# schematic_328.net
KiCad netlist of a schematic drawn in Altium Designer
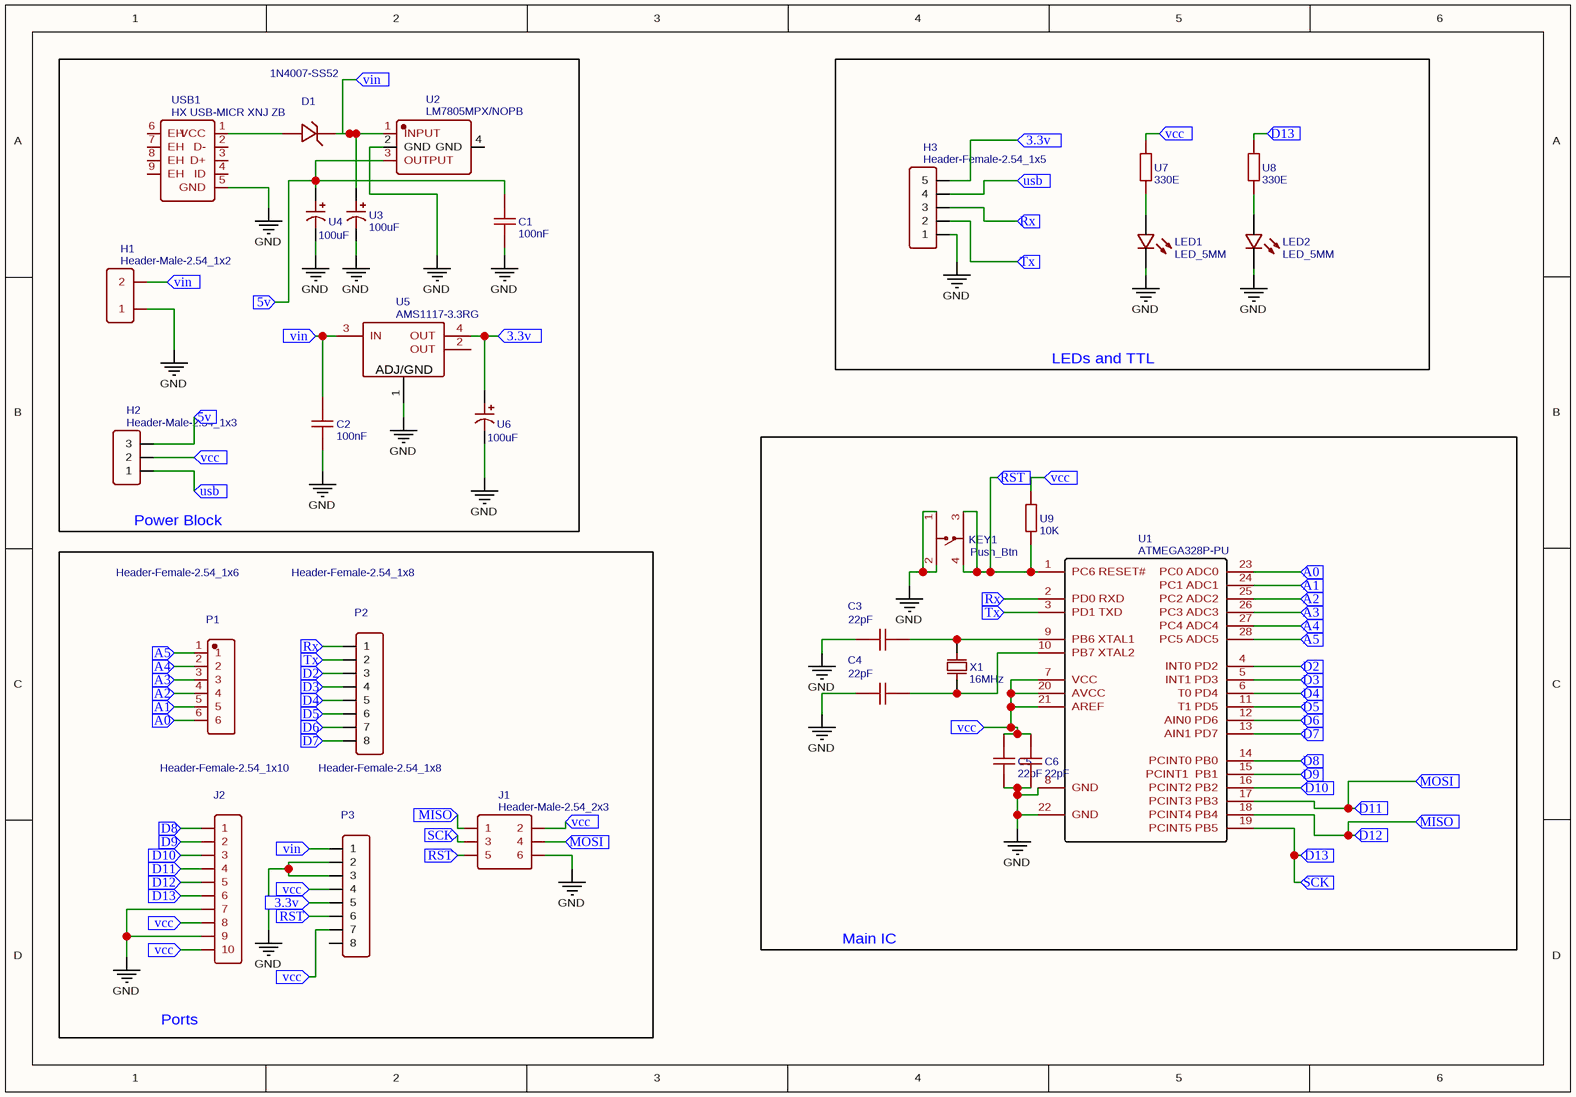
[diagram p0: schematic_328.schdoc]

(export (version "E")
  (design (tool "Eeschema 10.0.6"))
  (components
    (comp (ref "C1")
      (value "100nF")
      (fields
        (field (name "MANUFACTURER") "HRE(芯声)")
        (field (name "MANUFACTURER PART") "CGA1206X7R104K251NT")
        (field (name "CONTRIBUTOR") "lcsc")
      )
      (libsource (lib "altium-import") (part "root_1_100nF_"))
    )
    (comp (ref "C2")
      (value "100nF")
      (fields
        (field (name "MANUFACTURER") "HRE(芯声)")
        (field (name "MANUFACTURER PART") "CGA1206X7R104K251NT")
        (field (name "CONTRIBUTOR") "lcsc")
      )
      (libsource (lib "altium-import") (part "root_1_100nF_"))
    )
    (comp (ref "C3")
      (value "22pF")
      (fields
        (field (name "MANUFACTURER") "HRE(芯声)")
        (field (name "MANUFACTURER PART") "CGA1206X7R104K251NT")
        (field (name "CONTRIBUTOR") "lcsc")
      )
      (libsource (lib "altium-import") (part "root_2_22pF_"))
    )
    (comp (ref "C4")
      (value "22pF")
      (fields
        (field (name "MANUFACTURER") "HRE(芯声)")
        (field (name "MANUFACTURER PART") "CGA1206X7R104K251NT")
        (field (name "CONTRIBUTOR") "lcsc")
      )
      (libsource (lib "altium-import") (part "root_2_22pF_"))
    )
    (comp (ref "C5")
      (value "22pF")
      (fields
        (field (name "MANUFACTURER") "HRE(芯声)")
        (field (name "MANUFACTURER PART") "CGA1206X7R104K251NT")
        (field (name "CONTRIBUTOR") "lcsc")
      )
      (libsource (lib "altium-import") (part "root_3_22pF_"))
    )
    (comp (ref "C6")
      (value "22pF")
      (fields
        (field (name "MANUFACTURER") "HRE(芯声)")
        (field (name "MANUFACTURER PART") "CGA1206X7R104K251NT")
        (field (name "CONTRIBUTOR") "lcsc")
      )
      (libsource (lib "altium-import") (part "root_3_22pF_"))
    )
    (comp (ref "D1")
      (value "1N4007-SS52")
      (fields (field (name "CONTRIBUTOR") "LCSC"))
      (libsource (lib "altium-import") (part "root_2_1N4007-SS52_"))
    )
    (comp (ref "H1")
      (value "Header-Male-2.54_1x2")
      (fields
        (field (name "MANUFACTURER") "TE Connectivity(泰科电子)")
        (field (name "MANUFACTURER PART") "826629-2")
      )
      (libsource (lib "altium-import") (part "root_2_Header-Male-2.54_1x2_"))
    )
    (comp (ref "H2")
      (value "Header-Male-2.54_1x3")
      (fields (field (name "MANUFACTURER") "BOOMELE(博穆精密)") (field (name "MANUFACTURER PART") "2.54-1*3P针"))
      (libsource (lib "altium-import") (part "root_2_Header-Male-2.54_1x3_"))
    )
    (comp (ref "H3")
      (value "Header-Female-2.54_1x5")
      (fields (field (name "MANUFACTURER") "BOOMELE(博穆精密)") (field (name "MANUFACTURER PART") "2.54-1*5P母"))
      (libsource (lib "altium-import") (part "root_2_Header-Female-2.54_1x5_"))
    )
    (comp (ref "J1")
      (value "Header-Male-2.54_2x3")
      (fields (field (name "MANUFACTURER") "BOOMELE(博穆精密)") (field (name "MANUFACTURER PART") "2.54-2*3P针"))
      (libsource (lib "altium-import") (part "root_0_Header-Male-2.54_2x3_"))
    )
    (comp (ref "J2")
      (value "Header-Female-2.54_1x10")
      (fields (field (name "MANUFACTURER") "BOOMELE(博穆精密)") (field (name "MANUFACTURER PART") "2.54-1*10P母"))
      (libsource (lib "altium-import") (part "root_0_Header-Female-2.54_1x10_"))
    )
    (comp (ref "KEY1")
      (value "Push_Btn")
      (fields
        (field (name "MANUFACTURER PART") "4pinTACTPCBTHTPushButton")
        (field (name "CONTRIBUTOR") "LCSC")
      )
      (libsource (lib "altium-import") (part "root_1_Push_Btn_"))
    )
    (comp (ref "LED1")
      (value "LED_5MM")
      (fields (field (name "CONTRIBUTOR") "lcsc"))
      (libsource (lib "altium-import") (part "root_3_LED_5MM_"))
    )
    (comp (ref "LED2")
      (value "LED_5MM")
      (fields (field (name "CONTRIBUTOR") "lcsc"))
      (libsource (lib "altium-import") (part "root_3_LED_5MM_"))
    )
    (comp (ref "P1")
      (value "Header-Female-2.54_1x6")
      (fields (field (name "MANUFACTURER") "BOOMELE(博穆精密)") (field (name "MANUFACTURER PART") "2.54-1*6P母"))
      (libsource (lib "altium-import") (part "root_0_Header-Female-2.54_1x6_"))
    )
    (comp (ref "P2")
      (value "Header-Female-2.54_1x8")
      (fields (field (name "MANUFACTURER") "BOOMELE(博穆精密)") (field (name "MANUFACTURER PART") "2.54-1*8P母环保"))
      (libsource (lib "altium-import") (part "root_0_Header-Female-2.54_1x8_"))
    )
    (comp (ref "P3")
      (value "Header-Female-2.54_1x8")
      (fields (field (name "MANUFACTURER") "BOOMELE(博穆精密)") (field (name "MANUFACTURER PART") "2.54-1*8P母环保"))
      (libsource (lib "altium-import") (part "root_0_Header-Female-2.54_1x8_"))
    )
    (comp (ref "U1")
      (value "ATMEGA328P-PU")
      (fields (field (name "MANUFACTURER") "MICROCHIP(美国微芯)") (field (name "CONTRIBUTOR") "LCSC"))
      (libsource (lib "altium-import") (part "root_0_ATMEGA328P-PU_"))
    )
    (comp (ref "U2")
      (value "LM7805MPX/NOPB")
      (fields (field (name "MANUFACTURER") "TI(德州仪器)") (field (name "CONTRIBUTOR") "LCSC"))
      (libsource (lib "altium-import") (part "root_0_LM7805MPX/NOPB_"))
    )
    (comp (ref "U3")
      (value "100uF")
      (fields
        (field (name "MANUFACTURER") "rubycon(红宝石)")
        (field (name "MANUFACTURER PART") "25YXS100MEFC5X11")
        (field (name "CONTRIBUTOR") "lcsc")
      )
      (libsource (lib "altium-import") (part "root_3_100uF_"))
    )
    (comp (ref "U4")
      (value "100uF")
      (fields
        (field (name "MANUFACTURER") "rubycon(红宝石)")
        (field (name "MANUFACTURER PART") "25YXS100MEFC5X11")
        (field (name "CONTRIBUTOR") "lcsc")
      )
      (libsource (lib "altium-import") (part "root_3_100uF_"))
    )
    (comp (ref "U5")
      (value "AMS1117-3.3RG")
      (fields (field (name "MANUFACTURER") "HGC(深圳汉芯)") (field (name "CONTRIBUTOR") "lcsc"))
      (libsource (lib "altium-import") (part "root_0_AMS1117-3.3RG_"))
    )
    (comp (ref "U6")
      (value "100uF")
      (fields
        (field (name "MANUFACTURER") "rubycon(红宝石)")
        (field (name "MANUFACTURER PART") "25YXS100MEFC5X11")
        (field (name "CONTRIBUTOR") "lcsc")
      )
      (libsource (lib "altium-import") (part "root_3_100uF_"))
    )
    (comp (ref "U7")
      (value "330E")
      (fields (field (name "MANUFACTURER PART") "4703-1206") (field (name "CONTRIBUTOR") "lcsc"))
      (libsource (lib "altium-import") (part "root_1_330E_"))
    )
    (comp (ref "U8")
      (value "330E")
      (fields (field (name "MANUFACTURER PART") "4703-1206") (field (name "CONTRIBUTOR") "lcsc"))
      (libsource (lib "altium-import") (part "root_1_330E_"))
    )
    (comp (ref "U9")
      (value "10K")
      (fields (field (name "MANUFACTURER PART") "4703-1206") (field (name "CONTRIBUTOR") "lcsc"))
      (libsource (lib "altium-import") (part "root_1_10K_"))
    )
    (comp (ref "USB1")
      (value "HX USB-MICR XNJ ZB")
      (fields (field (name "MANUFACTURER") "hanxia(韩下)") (field (name "CONTRIBUTOR") "lcsc"))
      (libsource (lib "altium-import") (part "root_2_HX USB-MICR XNJ ZB_"))
    )
    (comp (ref "X1")
      (value "16MHz")
      (fields
        (field (name "MANUFACTURER") "JGHC(晶光华)")
        (field (name "MANUFACTURER PART") "49SAC16000202060")
        (field (name "CONTRIBUTOR") "LCSC")
      )
      (libsource (lib "altium-import") (part "root_1_16MHz_"))
    )
  )
  (nets
    (net (code "1") (name "/3.3v") (class "Default")
      (node (ref "H3") (pin "5") (pinfunction "5_5") (pintype "passive"))
      (node (ref "P3") (pin "5") (pinfunction "5_5") (pintype "passive"))
      (node (ref "U5") (pin "4") (pinfunction "OUT_4") (pintype "passive"))
      (node (ref "U6") (pin "1") (pinfunction "1_1") (pintype "passive"))
    )
    (net (code "2") (name "/5v") (class "Default")
      (node (ref "C1") (pin "2") (pinfunction "2_2") (pintype "passive"))
      (node (ref "H2") (pin "3") (pinfunction "3_3") (pintype "passive"))
      (node (ref "U2") (pin "3") (pinfunction "OUTPUT_3") (pintype "passive"))
      (node (ref "U4") (pin "1") (pinfunction "1_1") (pintype "passive"))
    )
    (net (code "3") (name "/A0") (class "Default")
      (node (ref "P1") (pin "6") (pinfunction "6_6") (pintype "passive"))
      (node (ref "U1") (pin "23") (pinfunction "PC0_ADC0_23") (pintype "passive"))
    )
    (net (code "4") (name "/A1") (class "Default")
      (node (ref "P1") (pin "5") (pinfunction "5_5") (pintype "passive"))
      (node (ref "U1") (pin "24") (pinfunction "PC1_ADC1_24") (pintype "passive"))
    )
    (net (code "5") (name "/A2") (class "Default")
      (node (ref "P1") (pin "4") (pinfunction "4_4") (pintype "passive"))
      (node (ref "U1") (pin "25") (pinfunction "PC2_ADC2_25") (pintype "passive"))
    )
    (net (code "6") (name "/A3") (class "Default")
      (node (ref "P1") (pin "3") (pinfunction "3_3") (pintype "passive"))
      (node (ref "U1") (pin "26") (pinfunction "PC3_ADC3_26") (pintype "passive"))
    )
    (net (code "7") (name "/A4") (class "Default")
      (node (ref "P1") (pin "2") (pinfunction "2_2") (pintype "passive"))
      (node (ref "U1") (pin "27") (pinfunction "PC4_ADC4_27") (pintype "passive"))
    )
    (net (code "8") (name "/A5") (class "Default")
      (node (ref "P1") (pin "1") (pinfunction "1_1") (pintype "passive"))
      (node (ref "U1") (pin "28") (pinfunction "PC5_ADC5_28") (pintype "passive"))
    )
    (net (code "9") (name "/D2") (class "Default")
      (node (ref "P2") (pin "3") (pinfunction "3_3") (pintype "passive"))
      (node (ref "U1") (pin "4") (pinfunction "INT0_PD2_4") (pintype "passive"))
    )
    (net (code "10") (name "/D3") (class "Default")
      (node (ref "P2") (pin "4") (pinfunction "4_4") (pintype "passive"))
      (node (ref "U1") (pin "5") (pinfunction "INT1_PD3_5") (pintype "passive"))
    )
    (net (code "11") (name "/D4") (class "Default")
      (node (ref "P2") (pin "5") (pinfunction "5_5") (pintype "passive"))
      (node (ref "U1") (pin "6") (pinfunction "T0_PD4_6") (pintype "passive"))
    )
    (net (code "12") (name "/D5") (class "Default")
      (node (ref "P2") (pin "6") (pinfunction "6_6") (pintype "passive"))
      (node (ref "U1") (pin "11") (pinfunction "T1_PD5_11") (pintype "passive"))
    )
    (net (code "13") (name "/D6") (class "Default")
      (node (ref "P2") (pin "7") (pinfunction "7_7") (pintype "passive"))
      (node (ref "U1") (pin "12") (pinfunction "AIN0_PD6_12") (pintype "passive"))
    )
    (net (code "14") (name "/D7") (class "Default")
      (node (ref "P2") (pin "8") (pinfunction "8_8") (pintype "passive"))
      (node (ref "U1") (pin "13") (pinfunction "AIN1_PD7_13") (pintype "passive"))
    )
    (net (code "15") (name "/D8") (class "Default")
      (node (ref "J2") (pin "1") (pinfunction "1_1") (pintype "passive"))
      (node (ref "U1") (pin "14") (pinfunction "PCINT0_PB0_14") (pintype "passive"))
    )
    (net (code "16") (name "/D9") (class "Default")
      (node (ref "J2") (pin "2") (pinfunction "2_2") (pintype "passive"))
      (node (ref "U1") (pin "15") (pinfunction "PCINT1__PB1_15") (pintype "passive"))
    )
    (net (code "17") (name "/D10") (class "Default")
      (node (ref "J2") (pin "3") (pinfunction "3_3") (pintype "passive"))
      (node (ref "U1") (pin "16") (pinfunction "PCINT2_PB2_16") (pintype "passive"))
    )
    (net (code "18") (name "/D11") (class "Default")
      (node (ref "J1") (pin "4") (pinfunction "4_4") (pintype "passive"))
      (node (ref "J2") (pin "4") (pinfunction "4_4") (pintype "passive"))
      (node (ref "U1") (pin "17") (pinfunction "PCINT3_PB3_17") (pintype "passive"))
    )
    (net (code "19") (name "/D12") (class "Default")
      (node (ref "J1") (pin "1") (pinfunction "1_1") (pintype "passive"))
      (node (ref "J2") (pin "5") (pinfunction "5_5") (pintype "passive"))
      (node (ref "U1") (pin "18") (pinfunction "PCINT4_PB4_18") (pintype "passive"))
    )
    (net (code "20") (name "/D13") (class "Default")
      (node (ref "J1") (pin "3") (pinfunction "3_3") (pintype "passive"))
      (node (ref "J2") (pin "6") (pinfunction "6_6") (pintype "passive"))
      (node (ref "U1") (pin "19") (pinfunction "PCINT5_PB5_19") (pintype "passive"))
      (node (ref "U8") (pin "2") (pinfunction "2_2") (pintype "passive"))
    )
    (net (code "21") (name "/RST") (class "Default")
      (node (ref "J1") (pin "5") (pinfunction "5_5") (pintype "passive"))
      (node (ref "KEY1") (pin "3") (pinfunction "3_3") (pintype "passive"))
      (node (ref "KEY1") (pin "4") (pinfunction "4_4") (pintype "passive"))
      (node (ref "P3") (pin "6") (pinfunction "6_6") (pintype "passive"))
      (node (ref "U1") (pin "1") (pinfunction "PC6_RESET#_1") (pintype "passive"))
      (node (ref "U9") (pin "1") (pinfunction "1_1") (pintype "passive"))
    )
    (net (code "22") (name "/Rx") (class "Default")
      (node (ref "H3") (pin "3") (pinfunction "3_3") (pintype "passive"))
      (node (ref "P2") (pin "1") (pinfunction "1_1") (pintype "passive"))
      (node (ref "U1") (pin "2") (pinfunction "PD0_RXD_2") (pintype "passive"))
    )
    (net (code "23") (name "/Tx") (class "Default")
      (node (ref "H3") (pin "2") (pinfunction "2_2") (pintype "passive"))
      (node (ref "P2") (pin "2") (pinfunction "2_2") (pintype "passive"))
      (node (ref "U1") (pin "3") (pinfunction "PD1_TXD_3") (pintype "passive"))
    )
    (net (code "24") (name "/usb") (class "Default")
      (node (ref "H2") (pin "1") (pinfunction "1_1") (pintype "passive"))
      (node (ref "H3") (pin "4") (pinfunction "4_4") (pintype "passive"))
    )
    (net (code "25") (name "/vcc") (class "Default")
      (node (ref "C5") (pin "1") (pinfunction "1_1") (pintype "passive"))
      (node (ref "C6") (pin "1") (pinfunction "1_1") (pintype "passive"))
      (node (ref "H2") (pin "2") (pinfunction "2_2") (pintype "passive"))
      (node (ref "J1") (pin "2") (pinfunction "2_2") (pintype "passive"))
      (node (ref "J2") (pin "10") (pinfunction "10_10") (pintype "passive"))
      (node (ref "J2") (pin "8") (pinfunction "8_8") (pintype "passive"))
      (node (ref "P3") (pin "4") (pinfunction "4_4") (pintype "passive"))
      (node (ref "P3") (pin "7") (pinfunction "7_7") (pintype "passive"))
      (node (ref "U1") (pin "20") (pinfunction "AVCC_20") (pintype "passive"))
      (node (ref "U1") (pin "21") (pinfunction "AREF_21") (pintype "passive"))
      (node (ref "U1") (pin "7") (pinfunction "VCC_7") (pintype "passive"))
      (node (ref "U7") (pin "2") (pinfunction "2_2") (pintype "passive"))
      (node (ref "U9") (pin "2") (pinfunction "2_2") (pintype "passive"))
    )
    (net (code "26") (name "/vin") (class "Default")
      (node (ref "C2") (pin "2") (pinfunction "2_2") (pintype "passive"))
      (node (ref "D1") (pin "1") (pinfunction "C_1") (pintype "passive"))
      (node (ref "H1") (pin "2") (pinfunction "2_2") (pintype "passive"))
      (node (ref "P3") (pin "1") (pinfunction "1_1") (pintype "passive"))
      (node (ref "U2") (pin "1") (pinfunction "INPUT_1") (pintype "passive"))
      (node (ref "U3") (pin "1") (pinfunction "1_1") (pintype "passive"))
      (node (ref "U5") (pin "3") (pinfunction "IN_3") (pintype "passive"))
    )
    (net (code "27") (name "GND") (class "Default")
      (node (ref "C1") (pin "1") (pinfunction "1_1") (pintype "passive"))
      (node (ref "C2") (pin "1") (pinfunction "1_1") (pintype "passive"))
      (node (ref "C3") (pin "2") (pinfunction "2_2") (pintype "passive"))
      (node (ref "C4") (pin "2") (pinfunction "2_2") (pintype "passive"))
      (node (ref "C5") (pin "2") (pinfunction "2_2") (pintype "passive"))
      (node (ref "C6") (pin "2") (pinfunction "2_2") (pintype "passive"))
      (node (ref "H1") (pin "1") (pinfunction "1_1") (pintype "passive"))
      (node (ref "H3") (pin "1") (pinfunction "1_1") (pintype "passive"))
      (node (ref "J1") (pin "6") (pinfunction "6_6") (pintype "passive"))
      (node (ref "J2") (pin "7") (pinfunction "7_7") (pintype "passive"))
      (node (ref "J2") (pin "9") (pinfunction "9_9") (pintype "passive"))
      (node (ref "KEY1") (pin "1") (pinfunction "1_1") (pintype "passive"))
      (node (ref "KEY1") (pin "2") (pinfunction "2_2") (pintype "passive"))
      (node (ref "LED1") (pin "2") (pinfunction "K_2") (pintype "passive"))
      (node (ref "LED2") (pin "2") (pinfunction "K_2") (pintype "passive"))
      (node (ref "P3") (pin "2") (pinfunction "2_2") (pintype "passive"))
      (node (ref "P3") (pin "3") (pinfunction "3_3") (pintype "passive"))
      (node (ref "U1") (pin "22") (pinfunction "GND_22") (pintype "passive"))
      (node (ref "U1") (pin "8") (pinfunction "GND_8") (pintype "passive"))
      (node (ref "U2") (pin "2") (pinfunction "GND_2") (pintype "passive"))
      (node (ref "U3") (pin "2") (pinfunction "2_2") (pintype "passive"))
      (node (ref "U4") (pin "2") (pinfunction "2_2") (pintype "passive"))
      (node (ref "U5") (pin "1") (pinfunction "ADJ/GND_1") (pintype "passive"))
      (node (ref "U6") (pin "2") (pinfunction "2_2") (pintype "passive"))
      (node (ref "USB1") (pin "5") (pinfunction "GND_5") (pintype "passive"))
    )
    (net (code "28") (name "Net-(D1-A)") (class "Default")
      (node (ref "D1") (pin "2") (pinfunction "A_2") (pintype "passive"))
      (node (ref "USB1") (pin "1") (pinfunction "VCC_1") (pintype "passive"))
    )
    (net (code "29") (name "Net-(LED1-A)") (class "Default")
      (node (ref "LED1") (pin "1") (pinfunction "A_1") (pintype "passive"))
      (node (ref "U7") (pin "1") (pinfunction "1_1") (pintype "passive"))
    )
    (net (code "30") (name "Net-(LED2-A)") (class "Default")
      (node (ref "LED2") (pin "1") (pinfunction "A_1") (pintype "passive"))
      (node (ref "U8") (pin "1") (pinfunction "1_1") (pintype "passive"))
    )
    (net (code "31") (name "Net-(U1-PB6_XTAL1)") (class "Default")
      (node (ref "C3") (pin "1") (pinfunction "1_1") (pintype "passive"))
      (node (ref "U1") (pin "9") (pinfunction "PB6_XTAL1_9") (pintype "passive"))
      (node (ref "X1") (pin "2") (pinfunction "OSC2_2") (pintype "passive"))
    )
    (net (code "32") (name "Net-(U1-PB7_XTAL2)") (class "Default")
      (node (ref "C4") (pin "1") (pinfunction "1_1") (pintype "passive"))
      (node (ref "U1") (pin "10") (pinfunction "PB7_XTAL2_10") (pintype "passive"))
      (node (ref "X1") (pin "1") (pinfunction "OSC1_1") (pintype "passive"))
    )
    (net (code "33") (name "unconnected-(P3-Pad8)") (class "Default")
      (node (ref "P3") (pin "8") (pinfunction "8_8") (pintype "passive"))
    )
    (net (code "34") (name "unconnected-(U2-GND-Pad4)") (class "Default")
      (node (ref "U2") (pin "4") (pinfunction "GND_4") (pintype "passive"))
    )
    (net (code "35") (name "unconnected-(U5-OUT-Pad2)") (class "Default")
      (node (ref "U5") (pin "2") (pinfunction "OUT_2") (pintype "passive"))
    )
    (net (code "36") (name "unconnected-(USB1-D+-Pad3)") (class "Default")
      (node (ref "USB1") (pin "3") (pinfunction "D+_3") (pintype "passive"))
    )
    (net (code "37") (name "unconnected-(USB1-D--Pad2)") (class "Default")
      (node (ref "USB1") (pin "2") (pinfunction "D-_2") (pintype "passive"))
    )
    (net (code "38") (name "unconnected-(USB1-EH-Pad6)") (class "Default")
      (node (ref "USB1") (pin "6") (pinfunction "EH_6") (pintype "passive"))
    )
    (net (code "39") (name "unconnected-(USB1-EH-Pad7)") (class "Default")
      (node (ref "USB1") (pin "7") (pinfunction "EH_7") (pintype "passive"))
    )
    (net (code "40") (name "unconnected-(USB1-EH-Pad8)") (class "Default")
      (node (ref "USB1") (pin "8") (pinfunction "EH_8") (pintype "passive"))
    )
    (net (code "41") (name "unconnected-(USB1-EH-Pad9)") (class "Default")
      (node (ref "USB1") (pin "9") (pinfunction "EH_9") (pintype "passive"))
    )
    (net (code "42") (name "unconnected-(USB1-ID-Pad4)") (class "Default")
      (node (ref "USB1") (pin "4") (pinfunction "ID_4") (pintype "passive"))
    )
  )
)
